# 8channel.net
KiCad netlist of a schematic drawn in EAGLE
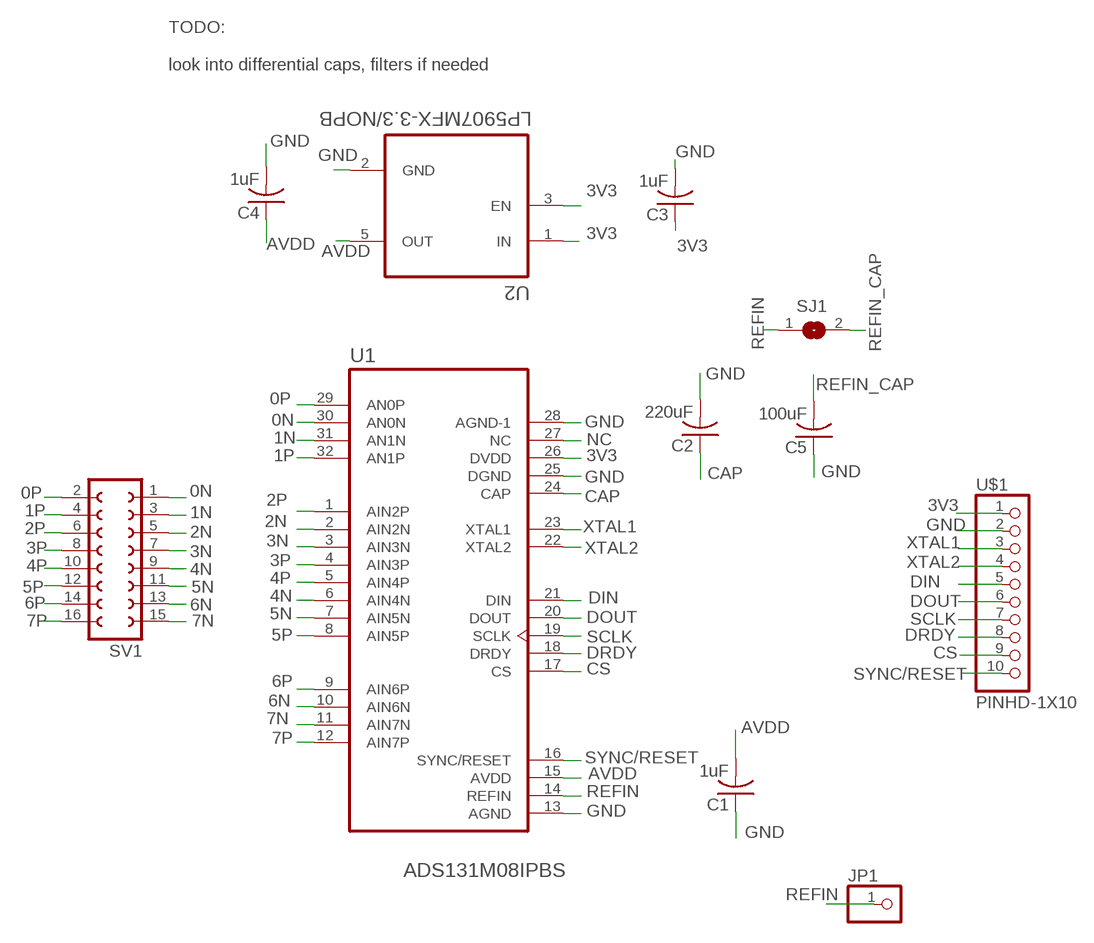
[diagram p0: schematic, sheet 1]

(export (version "E")
  (design (tool "Eeschema 10.0.6"))
  (components
    (comp (ref "C1")
      (value "1uF")
      (footprint "eagle-import:C0603")
      (libsource (lib "eagle-import") (part "C-USC0603"))
    )
    (comp (ref "C2")
      (value "220uF")
      (footprint "eagle-import:C0603")
      (libsource (lib "eagle-import") (part "C-USC0603"))
    )
    (comp (ref "C3")
      (value "1uF")
      (footprint "eagle-import:C0603")
      (libsource (lib "eagle-import") (part "C-USC0603"))
    )
    (comp (ref "C4")
      (value "1uF")
      (footprint "eagle-import:C0603")
      (libsource (lib "eagle-import") (part "C-USC0603"))
    )
    (comp (ref "C5")
      (value "100uF")
      (footprint "eagle-import:C0603")
      (libsource (lib "eagle-import") (part "C-USC0603"))
    )
    (comp (ref "JP1")
      (value "PINHD-1X1")
      (footprint "eagle-import:1X01")
      (libsource (lib "eagle-import") (part "PINHD-1X1"))
    )
    (comp (ref "SJ1") (value "SJ") (footprint "eagle-import:SJ") (libsource (lib "eagle-import") (part "SJ")))
    (comp (ref "SV1")
      (value "FE08-2")
      (footprint "eagle-import:FE08-2")
      (libsource (lib "eagle-import") (part "FE08-2"))
    )
    (comp (ref "U$1")
      (value "PINHD-1X10")
      (footprint "eagle-import:1X10-BIG")
      (libsource (lib "eagle-import") (part "PINHD-1X10"))
    )
    (comp (ref "U1")
      (value "ADS131M08IPBS")
      (footprint "eagle-import:QFP50P700X700X120-32N")
      (fields (field (name "MF") "Texas Instruments"))
      (libsource (lib "eagle-import") (part "ADS131M08IPBS"))
    )
    (comp (ref "U2")
      (value "LP5907MFX-3.3/NOPB")
      (footprint "eagle-import:SOT95P280X145-5N")
      (fields (field (name "MF") "Texas Instruments"))
      (libsource (lib "eagle-import") (part "LP5907MFX-3.3/NOPB"))
    )
  )
  (nets
    (net (code "1") (name "/0N") (class "Default")
      (node (ref "SV1") (pin "1") (pinfunction "1_1") (pintype "passive"))
      (node (ref "U1") (pin "30") (pinfunction "AN0N_30") (pintype "bidirectional"))
    )
    (net (code "2") (name "/0P") (class "Default")
      (node (ref "SV1") (pin "2") (pinfunction "2_2") (pintype "passive"))
      (node (ref "U1") (pin "29") (pinfunction "AN0P_29") (pintype "bidirectional"))
    )
    (net (code "3") (name "/1N") (class "Default")
      (node (ref "SV1") (pin "3") (pinfunction "3_3") (pintype "passive"))
      (node (ref "U1") (pin "31") (pinfunction "AN1N_31") (pintype "bidirectional"))
    )
    (net (code "4") (name "/1P") (class "Default")
      (node (ref "SV1") (pin "4") (pinfunction "4_4") (pintype "passive"))
      (node (ref "U1") (pin "32") (pinfunction "AN1P_32") (pintype "bidirectional"))
    )
    (net (code "5") (name "/2N") (class "Default")
      (node (ref "SV1") (pin "5") (pinfunction "5_5") (pintype "passive"))
      (node (ref "U1") (pin "2") (pinfunction "AIN2N_2") (pintype "input"))
    )
    (net (code "6") (name "/2P") (class "Default")
      (node (ref "SV1") (pin "6") (pinfunction "6_6") (pintype "passive"))
      (node (ref "U1") (pin "1") (pinfunction "AIN2P_1") (pintype "input"))
    )
    (net (code "7") (name "/3N") (class "Default")
      (node (ref "SV1") (pin "7") (pinfunction "7_7") (pintype "passive"))
      (node (ref "U1") (pin "3") (pinfunction "AIN3N_3") (pintype "input"))
    )
    (net (code "8") (name "/3P") (class "Default")
      (node (ref "SV1") (pin "8") (pinfunction "8_8") (pintype "passive"))
      (node (ref "U1") (pin "4") (pinfunction "AIN3P_4") (pintype "input"))
    )
    (net (code "9") (name "/3V3") (class "Default")
      (node (ref "C3") (pin "1") (pinfunction "1_1") (pintype "passive"))
      (node (ref "U$1") (pin "1") (pinfunction "1_1") (pintype "passive"))
      (node (ref "U1") (pin "26") (pinfunction "DVDD_26") (pintype "power_in"))
      (node (ref "U2") (pin "1") (pinfunction "IN_1") (pintype "input"))
      (node (ref "U2") (pin "3") (pinfunction "EN_3") (pintype "input"))
    )
    (net (code "10") (name "/4N") (class "Default")
      (node (ref "SV1") (pin "9") (pinfunction "9_9") (pintype "passive"))
      (node (ref "U1") (pin "6") (pinfunction "AIN4N_6") (pintype "input"))
    )
    (net (code "11") (name "/4P") (class "Default")
      (node (ref "SV1") (pin "10") (pinfunction "10_10") (pintype "passive"))
      (node (ref "U1") (pin "5") (pinfunction "AIN4P_5") (pintype "input"))
    )
    (net (code "12") (name "/5N") (class "Default")
      (node (ref "SV1") (pin "11") (pinfunction "11_11") (pintype "passive"))
      (node (ref "U1") (pin "7") (pinfunction "AIN5N_7") (pintype "input"))
    )
    (net (code "13") (name "/5P") (class "Default")
      (node (ref "SV1") (pin "12") (pinfunction "12_12") (pintype "passive"))
      (node (ref "U1") (pin "8") (pinfunction "AIN5P_8") (pintype "input"))
    )
    (net (code "14") (name "/6N") (class "Default")
      (node (ref "SV1") (pin "13") (pinfunction "13_13") (pintype "passive"))
      (node (ref "U1") (pin "10") (pinfunction "AIN6N_10") (pintype "input"))
    )
    (net (code "15") (name "/6P") (class "Default")
      (node (ref "SV1") (pin "14") (pinfunction "14_14") (pintype "passive"))
      (node (ref "U1") (pin "9") (pinfunction "AIN6P_9") (pintype "input"))
    )
    (net (code "16") (name "/7N") (class "Default")
      (node (ref "SV1") (pin "15") (pinfunction "15_15") (pintype "passive"))
      (node (ref "U1") (pin "11") (pinfunction "AIN7N_11") (pintype "input"))
    )
    (net (code "17") (name "/7P") (class "Default")
      (node (ref "SV1") (pin "16") (pinfunction "16_16") (pintype "passive"))
      (node (ref "U1") (pin "12") (pinfunction "AIN7P_12") (pintype "input"))
    )
    (net (code "18") (name "/AVDD") (class "Default")
      (node (ref "C1") (pin "2") (pinfunction "2_2") (pintype "passive"))
      (node (ref "C4") (pin "1") (pinfunction "1_1") (pintype "passive"))
      (node (ref "U1") (pin "15") (pinfunction "AVDD_15") (pintype "power_in"))
      (node (ref "U2") (pin "5") (pinfunction "OUT_5") (pintype "output"))
    )
    (net (code "19") (name "/CAP") (class "Default")
      (node (ref "C2") (pin "1") (pinfunction "1_1") (pintype "passive"))
      (node (ref "U1") (pin "24") (pinfunction "CAP_24") (pintype "bidirectional"))
    )
    (net (code "20") (name "/CS") (class "Default")
      (node (ref "U$1") (pin "9") (pinfunction "9_9") (pintype "passive"))
      (node (ref "U1") (pin "17") (pinfunction "CS_17") (pintype "bidirectional"))
    )
    (net (code "21") (name "/DIN") (class "Default")
      (node (ref "U$1") (pin "5") (pinfunction "5_5") (pintype "passive"))
      (node (ref "U1") (pin "21") (pinfunction "DIN_21") (pintype "input"))
    )
    (net (code "22") (name "/DOUT") (class "Default")
      (node (ref "U$1") (pin "6") (pinfunction "6_6") (pintype "passive"))
      (node (ref "U1") (pin "20") (pinfunction "DOUT_20") (pintype "output"))
    )
    (net (code "23") (name "/DRDY") (class "Default")
      (node (ref "U$1") (pin "8") (pinfunction "8_8") (pintype "passive"))
      (node (ref "U1") (pin "18") (pinfunction "DRDY_18") (pintype "output"))
    )
    (net (code "24") (name "/GND") (class "Default")
      (node (ref "C1") (pin "1") (pinfunction "1_1") (pintype "passive"))
      (node (ref "C2") (pin "2") (pinfunction "2_2") (pintype "passive"))
      (node (ref "C3") (pin "2") (pinfunction "2_2") (pintype "passive"))
      (node (ref "C4") (pin "2") (pinfunction "2_2") (pintype "passive"))
      (node (ref "C5") (pin "1") (pinfunction "1_1") (pintype "passive"))
      (node (ref "U$1") (pin "2") (pinfunction "2_2") (pintype "passive"))
      (node (ref "U1") (pin "13") (pinfunction "AGND_13") (pintype "power_in"))
      (node (ref "U1") (pin "25") (pinfunction "DGND_25") (pintype "power_in"))
      (node (ref "U1") (pin "28") (pinfunction "AGND-1_28") (pintype "power_in"))
      (node (ref "U2") (pin "2") (pinfunction "GND_2") (pintype "power_in"))
    )
    (net (code "25") (name "/NC") (class "Default")
      (node (ref "U1") (pin "27") (pinfunction "NC_27") (pintype "bidirectional"))
    )
    (net (code "26") (name "/REFIN") (class "Default")
      (node (ref "JP1") (pin "1") (pinfunction "1_1") (pintype "passive"))
      (node (ref "SJ1") (pin "1") (pinfunction "1_1") (pintype "passive"))
      (node (ref "U1") (pin "14") (pinfunction "REFIN_14") (pintype "input"))
    )
    (net (code "27") (name "/REFIN_CAP") (class "Default")
      (node (ref "C5") (pin "2") (pinfunction "2_2") (pintype "passive"))
      (node (ref "SJ1") (pin "2") (pinfunction "2_2") (pintype "passive"))
    )
    (net (code "28") (name "/SCLK") (class "Default")
      (node (ref "U$1") (pin "7") (pinfunction "7_7") (pintype "passive"))
      (node (ref "U1") (pin "19") (pinfunction "SCLK_19") (pintype "input"))
    )
    (net (code "29") (name "/SYNC{slash}RESET") (class "Default")
      (node (ref "U$1") (pin "10") (pinfunction "10_10") (pintype "passive"))
      (node (ref "U1") (pin "16") (pinfunction "SYNC/RESET_16") (pintype "bidirectional"))
    )
    (net (code "30") (name "/XTAL1") (class "Default")
      (node (ref "U$1") (pin "3") (pinfunction "3_3") (pintype "passive"))
      (node (ref "U1") (pin "23") (pinfunction "XTAL1_23") (pintype "bidirectional"))
    )
    (net (code "31") (name "/XTAL2") (class "Default")
      (node (ref "U$1") (pin "4") (pinfunction "4_4") (pintype "passive"))
      (node (ref "U1") (pin "22") (pinfunction "XTAL2_22") (pintype "bidirectional"))
    )
  )
)
